# Coil_Interface_Board.net
KiCad netlist of a schematic drawn in Altium Designer
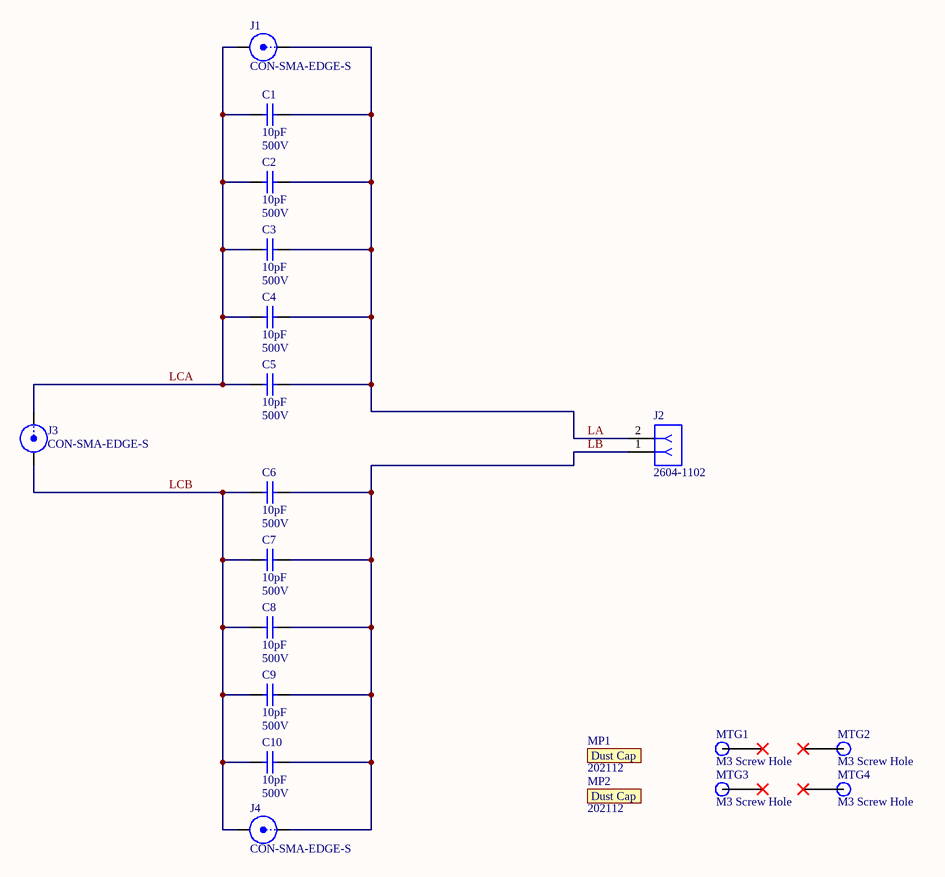
[diagram p0: Coil Interface Board.SchDoc]

(export (version "E")
  (design (tool "Eeschema 10.0.6"))
  (components
    (comp (ref "C1")
      (value "10pF")
      (footprint "CAP_1111_ATC 800B")
      (fields (field (name "VOLTAGE") "500V") (field (name "Comment") "800B100JT500XT1K"))
      (libsource (lib "University of Pennsylvania (ESE)") (part "cap"))
    )
    (comp (ref "C2")
      (value "10pF")
      (footprint "CAP_1111_ATC 800B")
      (fields (field (name "VOLTAGE") "500V") (field (name "Comment") "800B100JT500XT1K"))
      (libsource (lib "University of Pennsylvania (ESE)") (part "cap"))
    )
    (comp (ref "C3")
      (value "10pF")
      (footprint "CAP_1111_ATC 800B")
      (fields (field (name "VOLTAGE") "500V") (field (name "Comment") "800B100JT500XT1K"))
      (libsource (lib "University of Pennsylvania (ESE)") (part "cap"))
    )
    (comp (ref "C4")
      (value "10pF")
      (footprint "CAP_1111_ATC 800B")
      (fields (field (name "VOLTAGE") "500V") (field (name "Comment") "800B100JT500XT1K"))
      (libsource (lib "University of Pennsylvania (ESE)") (part "cap"))
    )
    (comp (ref "C5")
      (value "10pF")
      (footprint "CAP_1111_ATC 800B")
      (fields (field (name "VOLTAGE") "500V") (field (name "Comment") "800B100JT500XT1K"))
      (libsource (lib "University of Pennsylvania (ESE)") (part "cap"))
    )
    (comp (ref "C6")
      (value "10pF")
      (footprint "CAP_1111_ATC 800B")
      (fields (field (name "VOLTAGE") "500V") (field (name "Comment") "800B100JT500XT1K"))
      (libsource (lib "University of Pennsylvania (ESE)") (part "cap"))
    )
    (comp (ref "C7")
      (value "10pF")
      (footprint "CAP_1111_ATC 800B")
      (fields (field (name "VOLTAGE") "500V") (field (name "Comment") "800B100JT500XT1K"))
      (libsource (lib "University of Pennsylvania (ESE)") (part "cap"))
    )
    (comp (ref "C8")
      (value "10pF")
      (footprint "CAP_1111_ATC 800B")
      (fields (field (name "VOLTAGE") "500V") (field (name "Comment") "800B100JT500XT1K"))
      (libsource (lib "University of Pennsylvania (ESE)") (part "cap"))
    )
    (comp (ref "C9")
      (value "10pF")
      (footprint "CAP_1111_ATC 800B")
      (fields (field (name "VOLTAGE") "500V") (field (name "Comment") "800B100JT500XT1K"))
      (libsource (lib "University of Pennsylvania (ESE)") (part "cap"))
    )
    (comp (ref "C10")
      (value "10pF")
      (footprint "CAP_1111_ATC 800B")
      (fields (field (name "VOLTAGE") "500V") (field (name "Comment") "800B100JT500XT1K"))
      (libsource (lib "University of Pennsylvania (ESE)") (part "cap"))
    )
    (comp (ref "J1")
      (value "CON-SMA-EDGE-S")
      (footprint "FP-SMA-J-P-H-ST-EM1-MFG")
      (description "Sma Female Connector Jack, Pcb Edge Mount Rohs Compliant: Yes")
      (libsource (lib "University of Pennsylvania (ESE)") (part "RF Connector"))
    )
    (comp (ref "J2")
      (value "2604-1102")
      (footprint "2604-1102_MFG")
      (description "Pcb Terminal Block; Operating Lever; 4 MM²; Pin Spacing 5 Mm; 2-POLE; Push-in Cage Clamp®")
      (libsource (lib "University of Pennsylvania (ESE)") (part "Terminal 1X2"))
    )
    (comp (ref "J3")
      (value "CON-SMA-EDGE-S")
      (footprint "FP-SMA-J-P-H-ST-EM1-MFG")
      (description "Sma Female Connector Jack, Pcb Edge Mount Rohs Compliant: Yes")
      (libsource (lib "University of Pennsylvania (ESE)") (part "RF Connector"))
    )
    (comp (ref "J4")
      (value "CON-SMA-EDGE-S")
      (footprint "FP-SMA-J-P-H-ST-EM1-MFG")
      (description "Sma Female Connector Jack, Pcb Edge Mount Rohs Compliant: Yes")
      (libsource (lib "University of Pennsylvania (ESE)") (part "RF Connector"))
    )
    (comp (ref "MP1")
      (value "202112")
      (description "Amphenol RF 202112 SMA Cap for Female Connector, Brass/Gold")
      (libsource (lib "University of Pennsylvania (ESE)") (part "202112-Symbol-1"))
    )
    (comp (ref "MP2")
      (value "202112")
      (description "Amphenol RF 202112 SMA Cap for Female Connector, Brass/Gold")
      (libsource (lib "University of Pennsylvania (ESE)") (part "202112-Symbol-1"))
    )
    (comp (ref "MTG1")
      (value "M3 Screw Hole")
      (footprint "M3 Screw Hole-Footprint-1")
      (description "Close clearance Fit for M3 Screw Hole; PCB Mounting for M3 Screw")
      (libsource (lib "University of Pennsylvania (ESE)") (part "M3 Screw Hole-Symbol-1"))
    )
    (comp (ref "MTG2")
      (value "M3 Screw Hole")
      (footprint "M3 Screw Hole-Footprint-1")
      (description "Close clearance Fit for M3 Screw Hole; PCB Mounting for M3 Screw")
      (libsource (lib "University of Pennsylvania (ESE)") (part "M3 Screw Hole-Symbol-1"))
    )
    (comp (ref "MTG3")
      (value "M3 Screw Hole")
      (footprint "M3 Screw Hole-Footprint-1")
      (description "Close clearance Fit for M3 Screw Hole; PCB Mounting for M3 Screw")
      (libsource (lib "University of Pennsylvania (ESE)") (part "M3 Screw Hole-Symbol-1"))
    )
    (comp (ref "MTG4")
      (value "M3 Screw Hole")
      (footprint "M3 Screw Hole-Footprint-1")
      (description "Close clearance Fit for M3 Screw Hole; PCB Mounting for M3 Screw")
      (libsource (lib "University of Pennsylvania (ESE)") (part "M3 Screw Hole-Symbol-1"))
    )
  )
  (nets
    (net (code "1") (name "/LA") (class "Default")
      (node (ref "C1") (pin "2") (pinfunction "2_2") (pintype "passive"))
      (node (ref "C2") (pin "2") (pinfunction "2_2") (pintype "passive"))
      (node (ref "C3") (pin "2") (pinfunction "2_2") (pintype "passive"))
      (node (ref "C4") (pin "2") (pinfunction "2_2") (pintype "passive"))
      (node (ref "C5") (pin "2") (pinfunction "2_2") (pintype "passive"))
      (node (ref "J1") (pin "1") (pinfunction "1_1") (pintype "passive"))
      (node (ref "J2") (pin "2") (pinfunction "2_2") (pintype "passive"))
    )
    (net (code "2") (name "/LB") (class "Default")
      (node (ref "C10") (pin "2") (pinfunction "2_2") (pintype "passive"))
      (node (ref "C6") (pin "2") (pinfunction "2_2") (pintype "passive"))
      (node (ref "C7") (pin "2") (pinfunction "2_2") (pintype "passive"))
      (node (ref "C8") (pin "2") (pinfunction "2_2") (pintype "passive"))
      (node (ref "C9") (pin "2") (pinfunction "2_2") (pintype "passive"))
      (node (ref "J2") (pin "1") (pinfunction "1_1") (pintype "passive"))
      (node (ref "J4") (pin "1") (pinfunction "1_1") (pintype "passive"))
    )
    (net (code "3") (name "/LCA") (class "Default")
      (node (ref "C1") (pin "1") (pinfunction "1_1") (pintype "passive"))
      (node (ref "C2") (pin "1") (pinfunction "1_1") (pintype "passive"))
      (node (ref "C3") (pin "1") (pinfunction "1_1") (pintype "passive"))
      (node (ref "C4") (pin "1") (pinfunction "1_1") (pintype "passive"))
      (node (ref "C5") (pin "1") (pinfunction "1_1") (pintype "passive"))
      (node (ref "J1") (pin "2") (pinfunction "SHELL_2") (pintype "passive"))
      (node (ref "J3") (pin "1") (pinfunction "1_1") (pintype "passive"))
    )
    (net (code "4") (name "/LCB") (class "Default")
      (node (ref "C10") (pin "1") (pinfunction "1_1") (pintype "passive"))
      (node (ref "C6") (pin "1") (pinfunction "1_1") (pintype "passive"))
      (node (ref "C7") (pin "1") (pinfunction "1_1") (pintype "passive"))
      (node (ref "C8") (pin "1") (pinfunction "1_1") (pintype "passive"))
      (node (ref "C9") (pin "1") (pinfunction "1_1") (pintype "passive"))
      (node (ref "J3") (pin "2") (pinfunction "SHELL_2") (pintype "passive"))
      (node (ref "J4") (pin "2") (pinfunction "SHELL_2") (pintype "passive"))
    )
    (net (code "5") (name "unconnected-(MTG1-Pad1)") (class "Default")
      (node (ref "MTG1") (pin "1") (pinfunction "1_1") (pintype "passive+no_connect"))
    )
    (net (code "6") (name "unconnected-(MTG2-Pad1)") (class "Default")
      (node (ref "MTG2") (pin "1") (pinfunction "1_1") (pintype "passive+no_connect"))
    )
    (net (code "7") (name "unconnected-(MTG3-Pad1)") (class "Default")
      (node (ref "MTG3") (pin "1") (pinfunction "1_1") (pintype "passive+no_connect"))
    )
    (net (code "8") (name "unconnected-(MTG4-Pad1)") (class "Default")
      (node (ref "MTG4") (pin "1") (pinfunction "1_1") (pintype "passive+no_connect"))
    )
  )
)
